# 07_USB.net
KiCad netlist of a schematic drawn in Altium Designer
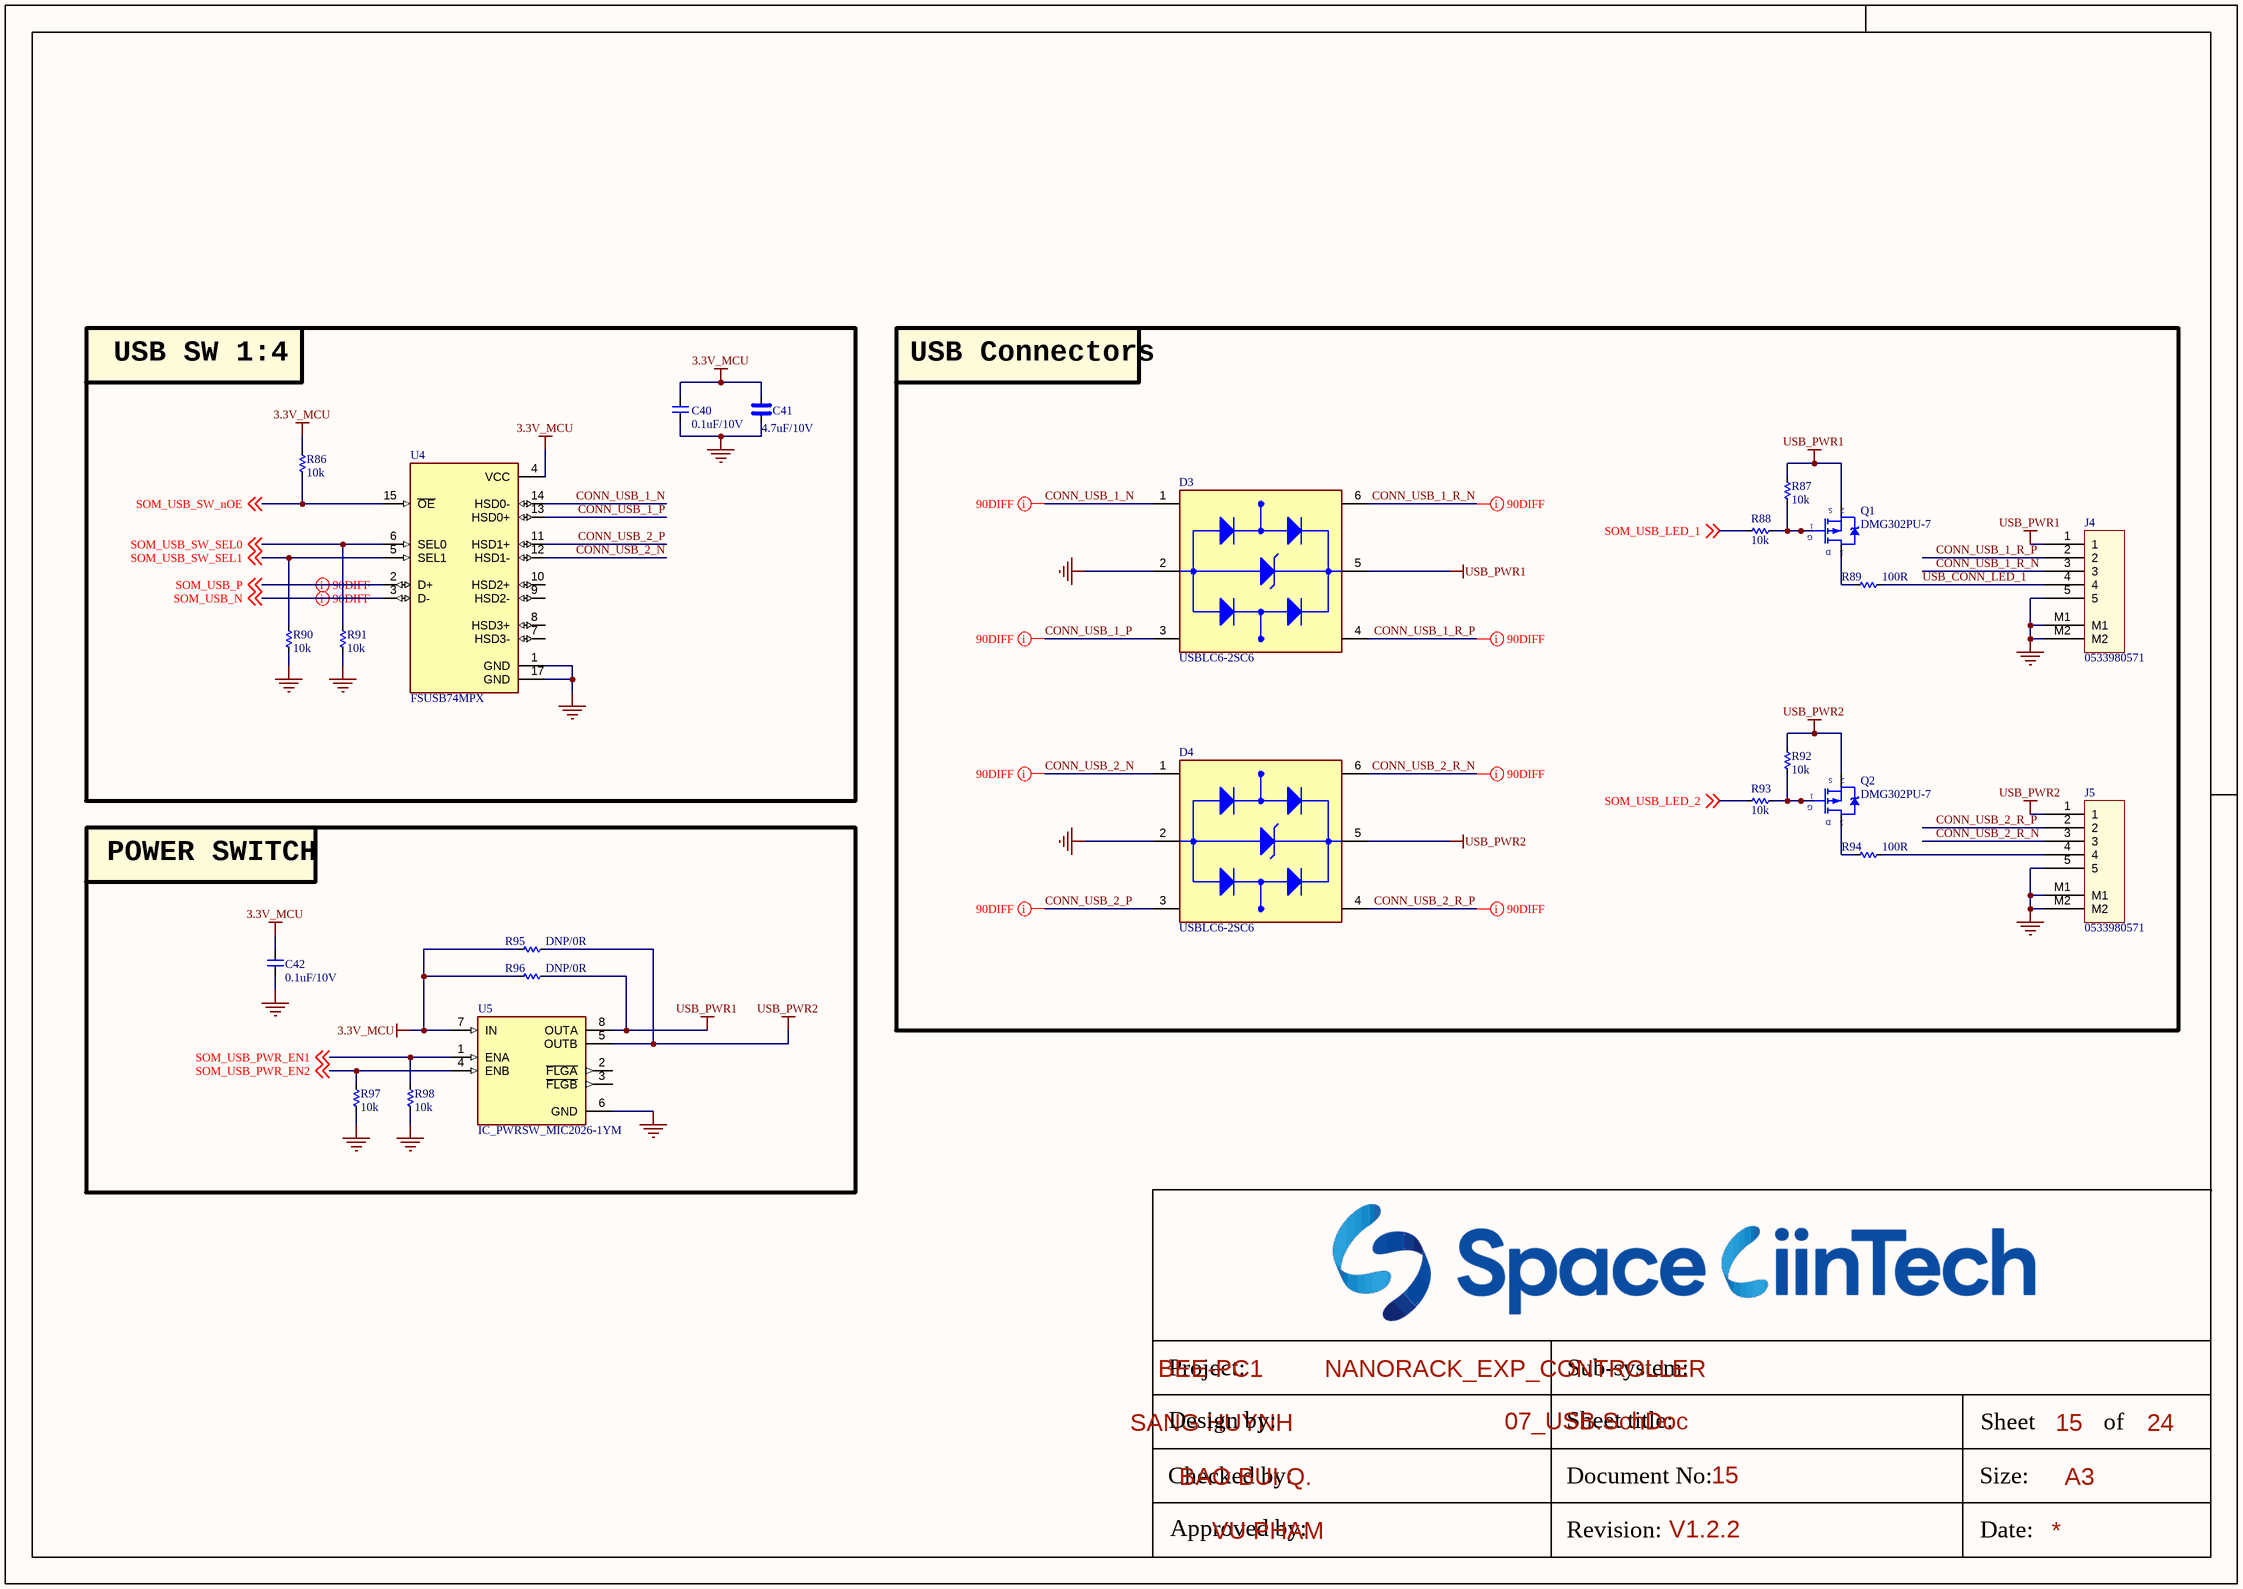
[diagram p0: 07_USB.SchDoc]

(export (version "E")
  (design (tool "Eeschema 10.0.6"))
  (components
    (comp (ref "C40")
      (value "0.1uF/10V")
      (footprint "CAP_C_1005X60")
      (description "CAP CHIP")
      (libsource (lib "LABLIB") (part "_CAP_C_2"))
    )
    (comp (ref "C41")
      (value "4.7uF/10V")
      (footprint "CAP_C_1608X80")
      (description "CAP CHIP High Value")
      (libsource (lib "LABLIB") (part "_CAP_C_High_2"))
    )
    (comp (ref "C42")
      (value "0.1uF/10V")
      (footprint "CAP_C_1005X60")
      (description "CAP CHIP")
      (libsource (lib "LABLIB") (part "_CAP_C_2"))
    )
    (comp (ref "D3")
      (value "USBLC6-2SC6")
      (footprint "SOT95P280X145-6N")
      (description "17V Clamp 5A (8/20Âµs) Ipp Tvs Diode Surface Mount SOT-23-6")
      (fields (field (name "MF") "STMicroelectronics"))
      (libsource (lib "USBLC6-2SC6") (part "USBLC6-2SC6"))
    )
    (comp (ref "D4")
      (value "USBLC6-2SC6")
      (footprint "SOT95P280X145-6N")
      (description "17V Clamp 5A (8/20Âµs) Ipp Tvs Diode Surface Mount SOT-23-6")
      (fields (field (name "MF") "STMicroelectronics"))
      (libsource (lib "USBLC6-2SC6") (part "USBLC6-2SC6"))
    )
    (comp (ref "J4")
      (value "0533980571")
      (footprint "MOLEX_0533980571")
      (libsource (lib "LABLIB") (part "Header 5x1_2M"))
    )
    (comp (ref "J5")
      (value "0533980571")
      (footprint "MOLEX_0533980571")
      (libsource (lib "LABLIB") (part "Header 5x1_2M"))
    )
    (comp (ref "Q1")
      (value "DMG302PU-7")
      (footprint "SOT95P240X120-3N")
      (libsource (lib "LABLIB") (part "MOSFET_P_GSD"))
    )
    (comp (ref "Q2")
      (value "DMG302PU-7")
      (footprint "SOT95P240X120-3N")
      (libsource (lib "LABLIB") (part "MOSFET_P_GSD"))
    )
    (comp (ref "R86")
      (value "10k")
      (footprint "RES_C_1005X40")
      (description "RES")
      (libsource (lib "LABLIB") (part "_RES_B_2"))
    )
    (comp (ref "R87")
      (value "10k")
      (footprint "RES_C_1005X40")
      (description "RES")
      (libsource (lib "LABLIB") (part "_RES_B_2"))
    )
    (comp (ref "R88")
      (value "10k")
      (footprint "RES_C_1005X40")
      (description "RES")
      (libsource (lib "LABLIB") (part "_RES_B_2"))
    )
    (comp (ref "R89")
      (value "100R")
      (footprint "RES_C_1005X40")
      (description "RES")
      (libsource (lib "LABLIB") (part "_RES_B_2"))
    )
    (comp (ref "R90")
      (value "10k")
      (footprint "RES_C_1005X40")
      (description "RES")
      (libsource (lib "LABLIB") (part "_RES_B_2"))
    )
    (comp (ref "R91")
      (value "10k")
      (footprint "RES_C_1005X40")
      (description "RES")
      (libsource (lib "LABLIB") (part "_RES_B_2"))
    )
    (comp (ref "R92")
      (value "10k")
      (footprint "RES_C_1005X40")
      (description "RES")
      (libsource (lib "LABLIB") (part "_RES_B_2"))
    )
    (comp (ref "R93")
      (value "10k")
      (footprint "RES_C_1005X40")
      (description "RES")
      (libsource (lib "LABLIB") (part "_RES_B_2"))
    )
    (comp (ref "R94")
      (value "100R")
      (footprint "RES_C_1005X40")
      (description "RES")
      (libsource (lib "LABLIB") (part "_RES_B_2"))
    )
    (comp (ref "R95")
      (value "DNP/0R")
      (footprint "RES_C_1005X40")
      (description "RES")
      (libsource (lib "LABLIB") (part "_RES_B_2"))
    )
    (comp (ref "R96")
      (value "DNP/0R")
      (footprint "RES_C_1005X40")
      (description "RES")
      (libsource (lib "LABLIB") (part "_RES_B_2"))
    )
    (comp (ref "R97")
      (value "10k")
      (footprint "RES_C_1005X40")
      (description "RES")
      (libsource (lib "LABLIB") (part "_RES_B_2"))
    )
    (comp (ref "R98")
      (value "10k")
      (footprint "RES_C_1005X40")
      (description "RES")
      (libsource (lib "LABLIB") (part "_RES_B_2"))
    )
    (comp (ref "U4")
      (value "FSUSB74MPX")
      (footprint "QFN50P300X300X80-17N")
      (description "USB Switch IC 1 Channel 16-MLP (3x3)")
      (fields (field (name "MF") "ON Semiconductor"))
      (libsource (lib "LABLIB") (part "IC_USB_SW_FSUSB74MPX"))
    )
    (comp (ref "U5")
      (value "IC_PWRSW_MIC2026-1YM")
      (footprint "SOIC127P602X173-8N")
      (description "Power Switch/Driver 1:2 N-Channel 1.25A 8-SOIC")
      (fields (field (name "MF") "Microchip") (field (name "MP") "MIC2026-1YM"))
      (libsource (lib "LABLIB") (part "IC_PWRSW_MIC2026-1YM"))
    )
  )
  (nets
    (net (code "1") (name "/CONN_USB_1_N") (class "Default")
      (node (ref "D3") (pin "1") (pinfunction "I/O1_IN_1") (pintype "passive"))
      (node (ref "U4") (pin "14") (pinfunction "HSD0-_14") (pintype "bidirectional"))
    )
    (net (code "2") (name "/CONN_USB_1_P") (class "Default")
      (node (ref "D3") (pin "3") (pinfunction "I/O2_IN_3") (pintype "passive"))
      (node (ref "U4") (pin "13") (pinfunction "HSD0+_13") (pintype "bidirectional"))
    )
    (net (code "3") (name "/CONN_USB_1_R_N") (class "Default")
      (node (ref "D3") (pin "6") (pinfunction "I/O1_OUT_6") (pintype "passive"))
      (node (ref "J4") (pin "3") (pinfunction "3_3") (pintype "passive"))
    )
    (net (code "4") (name "/CONN_USB_1_R_P") (class "Default")
      (node (ref "D3") (pin "4") (pinfunction "I/O2_OUT_4") (pintype "passive"))
      (node (ref "J4") (pin "2") (pinfunction "2_2") (pintype "passive"))
    )
    (net (code "5") (name "/CONN_USB_2_N") (class "Default")
      (node (ref "D4") (pin "1") (pinfunction "I/O1_IN_1") (pintype "passive"))
      (node (ref "U4") (pin "12") (pinfunction "HSD1-_12") (pintype "bidirectional"))
    )
    (net (code "6") (name "/CONN_USB_2_P") (class "Default")
      (node (ref "D4") (pin "3") (pinfunction "I/O2_IN_3") (pintype "passive"))
      (node (ref "U4") (pin "11") (pinfunction "HSD1+_11") (pintype "bidirectional"))
    )
    (net (code "7") (name "/CONN_USB_2_R_N") (class "Default")
      (node (ref "D4") (pin "6") (pinfunction "I/O1_OUT_6") (pintype "passive"))
      (node (ref "J5") (pin "3") (pinfunction "3_3") (pintype "passive"))
    )
    (net (code "8") (name "/CONN_USB_2_R_P") (class "Default")
      (node (ref "D4") (pin "4") (pinfunction "I/O2_OUT_4") (pintype "passive"))
      (node (ref "J5") (pin "2") (pinfunction "2_2") (pintype "passive"))
    )
    (net (code "9") (name "/USB_CONN_LED_1") (class "Default")
      (node (ref "J4") (pin "4") (pinfunction "4_4") (pintype "passive"))
      (node (ref "R89") (pin "2") (pinfunction "2_2") (pintype "passive"))
    )
    (net (code "10") (name "3.3V_MCU") (class "Default")
      (node (ref "C40") (pin "2") (pinfunction "2_2") (pintype "passive"))
      (node (ref "C41") (pin "2") (pinfunction "2_2") (pintype "passive"))
      (node (ref "C42") (pin "2") (pinfunction "2_2") (pintype "passive"))
      (node (ref "R86") (pin "1") (pinfunction "1_1") (pintype "passive"))
      (node (ref "R95") (pin "2") (pinfunction "2_2") (pintype "passive"))
      (node (ref "R96") (pin "2") (pinfunction "2_2") (pintype "passive"))
      (node (ref "U4") (pin "4") (pinfunction "VCC_4") (pintype "power_in"))
      (node (ref "U5") (pin "7") (pinfunction "IN_7") (pintype "input"))
    )
    (net (code "11") (name "GND") (class "Default")
      (node (ref "C40") (pin "1") (pinfunction "1_1") (pintype "passive"))
      (node (ref "C41") (pin "1") (pinfunction "1_1") (pintype "passive"))
      (node (ref "C42") (pin "1") (pinfunction "1_1") (pintype "passive"))
      (node (ref "D3") (pin "2") (pinfunction "GND_2") (pintype "power_in"))
      (node (ref "D4") (pin "2") (pinfunction "GND_2") (pintype "power_in"))
      (node (ref "J4") (pin "5") (pinfunction "5_5") (pintype "passive"))
      (node (ref "J4") (pin "M1") (pinfunction "M1_M1") (pintype "passive"))
      (node (ref "J4") (pin "M2") (pinfunction "M2_M2") (pintype "passive"))
      (node (ref "J5") (pin "5") (pinfunction "5_5") (pintype "passive"))
      (node (ref "J5") (pin "M1") (pinfunction "M1_M1") (pintype "passive"))
      (node (ref "J5") (pin "M2") (pinfunction "M2_M2") (pintype "passive"))
      (node (ref "R90") (pin "2") (pinfunction "2_2") (pintype "passive"))
      (node (ref "R91") (pin "2") (pinfunction "2_2") (pintype "passive"))
      (node (ref "R97") (pin "2") (pinfunction "2_2") (pintype "passive"))
      (node (ref "R98") (pin "2") (pinfunction "2_2") (pintype "passive"))
      (node (ref "U4") (pin "1") (pinfunction "GND_1") (pintype "power_in"))
      (node (ref "U4") (pin "17") (pinfunction "GND_17") (pintype "power_in"))
      (node (ref "U5") (pin "6") (pinfunction "GND_6") (pintype "power_in"))
    )
    (net (code "12") (name "Net-(J5-Pad4)") (class "Default")
      (node (ref "J5") (pin "4") (pinfunction "4_4") (pintype "passive"))
      (node (ref "R94") (pin "2") (pinfunction "2_2") (pintype "passive"))
    )
    (net (code "13") (name "Net-(Q1-D)") (class "Default")
      (node (ref "Q1") (pin "3") (pinfunction "D_3") (pintype "passive"))
      (node (ref "R89") (pin "1") (pinfunction "1_1") (pintype "passive"))
    )
    (net (code "14") (name "Net-(Q1-G)") (class "Default")
      (node (ref "Q1") (pin "1") (pinfunction "G_1") (pintype "passive"))
      (node (ref "R87") (pin "2") (pinfunction "2_2") (pintype "passive"))
      (node (ref "R88") (pin "2") (pinfunction "2_2") (pintype "passive"))
    )
    (net (code "15") (name "Net-(Q2-D)") (class "Default")
      (node (ref "Q2") (pin "3") (pinfunction "D_3") (pintype "passive"))
      (node (ref "R94") (pin "1") (pinfunction "1_1") (pintype "passive"))
    )
    (net (code "16") (name "Net-(Q2-G)") (class "Default")
      (node (ref "Q2") (pin "1") (pinfunction "G_1") (pintype "passive"))
      (node (ref "R92") (pin "2") (pinfunction "2_2") (pintype "passive"))
      (node (ref "R93") (pin "2") (pinfunction "2_2") (pintype "passive"))
    )
    (net (code "17") (name "SOM_USB_LED_1") (class "Default")
      (node (ref "R88") (pin "1") (pinfunction "1_1") (pintype "passive"))
    )
    (net (code "18") (name "SOM_USB_LED_2") (class "Default")
      (node (ref "R93") (pin "1") (pinfunction "1_1") (pintype "passive"))
    )
    (net (code "19") (name "SOM_USB_N") (class "Default")
      (node (ref "U4") (pin "3") (pinfunction "D-_3") (pintype "bidirectional"))
    )
    (net (code "20") (name "SOM_USB_P") (class "Default")
      (node (ref "U4") (pin "2") (pinfunction "D+_2") (pintype "bidirectional"))
    )
    (net (code "21") (name "SOM_USB_PWR_EN1") (class "Default")
      (node (ref "R98") (pin "1") (pinfunction "1_1") (pintype "passive"))
      (node (ref "U5") (pin "1") (pinfunction "ENA_1") (pintype "input"))
    )
    (net (code "22") (name "SOM_USB_PWR_EN2") (class "Default")
      (node (ref "R97") (pin "1") (pinfunction "1_1") (pintype "passive"))
      (node (ref "U5") (pin "4") (pinfunction "ENB_4") (pintype "input"))
    )
    (net (code "23") (name "SOM_USB_SW_SEL0") (class "Default")
      (node (ref "R91") (pin "1") (pinfunction "1_1") (pintype "passive"))
      (node (ref "U4") (pin "6") (pinfunction "SEL0_6") (pintype "input"))
    )
    (net (code "24") (name "SOM_USB_SW_SEL1") (class "Default")
      (node (ref "R90") (pin "1") (pinfunction "1_1") (pintype "passive"))
      (node (ref "U4") (pin "5") (pinfunction "SEL1_5") (pintype "input"))
    )
    (net (code "25") (name "SOM_USB_SW_nOE") (class "Default")
      (node (ref "R86") (pin "2") (pinfunction "2_2") (pintype "passive"))
      (node (ref "U4") (pin "15") (pinfunction "~{OE}_15") (pintype "input"))
    )
    (net (code "26") (name "USB_PWR1") (class "Default")
      (node (ref "D3") (pin "5") (pinfunction "VBUS_5") (pintype "power_in"))
      (node (ref "J4") (pin "1") (pinfunction "1_1") (pintype "passive"))
      (node (ref "Q1") (pin "2") (pinfunction "S_2") (pintype "passive"))
      (node (ref "R87") (pin "1") (pinfunction "1_1") (pintype "passive"))
      (node (ref "R96") (pin "1") (pinfunction "1_1") (pintype "passive"))
      (node (ref "U5") (pin "8") (pinfunction "OUTA_8") (pintype "passive"))
    )
    (net (code "27") (name "USB_PWR2") (class "Default")
      (node (ref "D4") (pin "5") (pinfunction "VBUS_5") (pintype "power_in"))
      (node (ref "J5") (pin "1") (pinfunction "1_1") (pintype "passive"))
      (node (ref "Q2") (pin "2") (pinfunction "S_2") (pintype "passive"))
      (node (ref "R92") (pin "1") (pinfunction "1_1") (pintype "passive"))
      (node (ref "R95") (pin "1") (pinfunction "1_1") (pintype "passive"))
      (node (ref "U5") (pin "5") (pinfunction "OUTB_5") (pintype "passive"))
    )
    (net (code "28") (name "unconnected-(U4-HSD2+-Pad10)") (class "Default")
      (node (ref "U4") (pin "10") (pinfunction "HSD2+_10") (pintype "bidirectional"))
    )
    (net (code "29") (name "unconnected-(U4-HSD2--Pad9)") (class "Default")
      (node (ref "U4") (pin "9") (pinfunction "HSD2-_9") (pintype "bidirectional"))
    )
    (net (code "30") (name "unconnected-(U4-HSD3+-Pad8)") (class "Default")
      (node (ref "U4") (pin "8") (pinfunction "HSD3+_8") (pintype "bidirectional"))
    )
    (net (code "31") (name "unconnected-(U4-HSD3--Pad7)") (class "Default")
      (node (ref "U4") (pin "7") (pinfunction "HSD3-_7") (pintype "bidirectional"))
    )
    (net (code "32") (name "unconnected-(U5-~{FLGA}-Pad2)") (class "Default")
      (node (ref "U5") (pin "2") (pinfunction "~{FLGA}_2") (pintype "output"))
    )
    (net (code "33") (name "unconnected-(U5-~{FLGB}-Pad3)") (class "Default")
      (node (ref "U5") (pin "3") (pinfunction "~{FLGB}_3") (pintype "output"))
    )
  )
)
